# WX0_008_959DL.net
KiCad netlist of a schematic drawn in Altium Designer
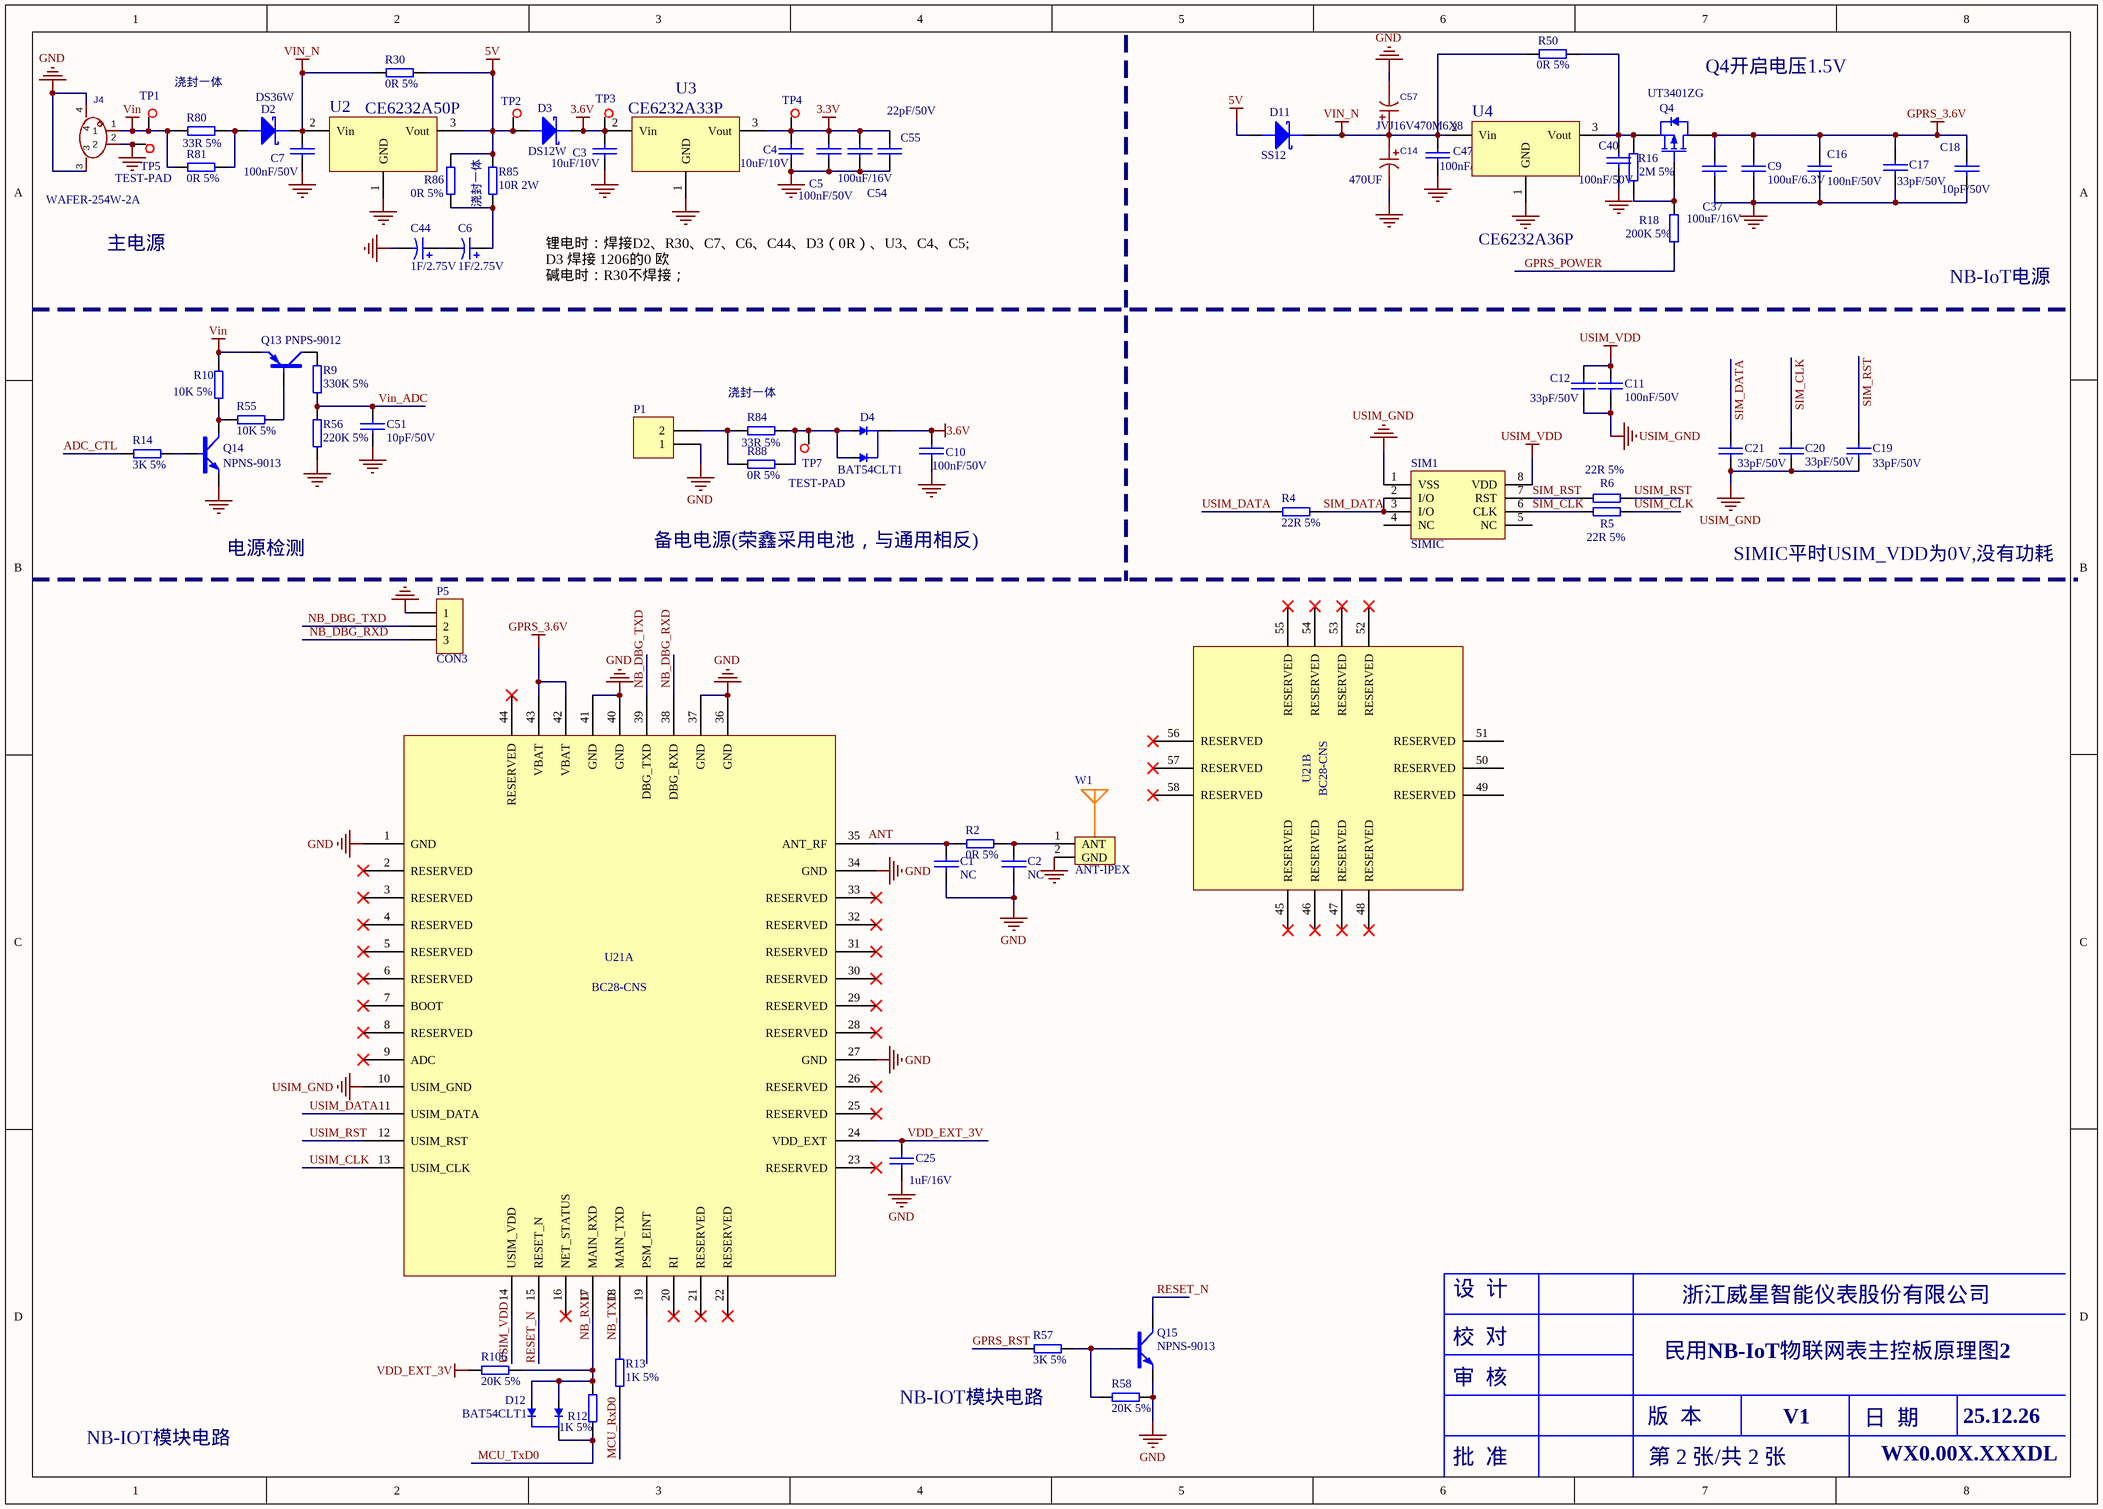
[diagram p0: WX0.008.959DL.SchDoc]

(export (version "E")
  (design (tool "Eeschema 10.0.6"))
  (components
    (comp (ref "C1")
      (value "NC")
      (footprint "CAP0402")
      (fields (field (name "PART NUMBER") "101020103-0005"))
      (libsource (lib "Database_Libs2") (part "CC03JPO9_12P"))
    )
    (comp (ref "C2")
      (value "NC")
      (footprint "CAP0402")
      (fields (field (name "PART NUMBER") "101020103-0005"))
      (libsource (lib "Database_Libs2") (part "CC03JPO9_12P"))
    )
    (comp (ref "C3")
      (value "10uF/10V")
      (footprint "CAP0603")
      (description "106pF,10 V,±10%,0603,村田,GRM188R61A106KE47D")
      (fields (field (name "PART NUMBER") "101020103-0026"))
      (libsource (lib "Database_Libs2") (part "CC03K5R6_10U"))
    )
    (comp (ref "C4")
      (value "10uF/10V")
      (footprint "CAP0603")
      (description "106pF,10 V,±10%,0603,村田,GRM188R61A106KE47D")
      (fields (field (name "PART NUMBER") "101020103-0026"))
      (libsource (lib "Database_Libs2") (part "CC03K5R6_10U"))
    )
    (comp (ref "C5")
      (value "100nF/50V")
      (footprint "CAP0603")
      (description "104pF,50 V,±10%,0603,国巨,CC0603KRX7R9BB104")
      (fields (field (name "PART NUMBER") "101020103-0021"))
      (libsource (lib "Database_Libs2") (part "CC03K7R9_100N"))
    )
    (comp (ref "C6")
      (value "1F/2.75V")
      (footprint "CAPPC_350_800_1600")
      (description "1F,2.75 V,-20%~+20%,8mm*16mm,红宝石,2.7 DMC 1 M MY4 8X16")
      (fields (field (name "PART NUMBER") "1010202-0015"))
      (libsource (lib "Database_Libs2") (part "CALM3MRDMC_1F"))
    )
    (comp (ref "C7")
      (value "100nF/50V")
      (footprint "CAP0603")
      (description "104pF,50 V,±10%,0603,国巨,CC0603KRX7R9BB104")
      (fields (field (name "PART NUMBER") "101020103-0021"))
      (libsource (lib "Database_Libs2") (part "CC03K7R9_100N"))
    )
    (comp (ref "C9")
      (value "100uF/6.3V")
      (footprint "GRM1206")
      (description "100uF,6.3 V,±20%,1206,村田,GRM31CR60J107ME39L")
      (fields (field (name "PART NUMBER") "101020101-0020"))
      (libsource (lib "Database_Libs2") (part "CC06M5R5_107P"))
    )
    (comp (ref "C10")
      (value "100nF/50V")
      (footprint "CAP0603")
      (description "104pF,50 V,±10%,0603,国巨,CC0603KRX7R9BB104")
      (fields (field (name "PART NUMBER") "101020103-0021"))
      (libsource (lib "Database_Libs2") (part "CC03K7R9_100N"))
    )
    (comp (ref "C11")
      (value "100nF/50V")
      (footprint "CAP0603")
      (description "104pF,50 V,±10%,0603,国巨,CC0603KRX7R9BB104")
      (fields (field (name "PART NUMBER") "101020103-0021"))
      (libsource (lib "Database_Libs2") (part "CC03K7R9_100N"))
    )
    (comp (ref "C12")
      (value "33pF/50V")
      (footprint "CAP0603")
      (description "33pF,50 V,±10%,0603,国巨,CC0603KRNPO9BN33")
      (fields (field (name "PART NUMBER") "101020103-0027"))
      (libsource (lib "Database_Libs2") (part "CC03KPO9_33P"))
    )
    (comp (ref "C14")
      (value "470UF")
      (footprint "CAP-SMD_BD6.3-L6.6-W6.6-LS7.3-FD-H7.7")
      (description "470UF,10v")
      (libsource (lib "JVJ16V470M6X8JVJ16V470M6X8") (part "JVJ16V470M6X8"))
    )
    (comp (ref "C16")
      (value "100nF/50V")
      (footprint "CAP0603")
      (description "104pF,50 V,±10%,0603,国巨,CC0603KRX7R9BB104")
      (fields (field (name "PART NUMBER") "101020103-0021"))
      (libsource (lib "Database_Libs2") (part "CC03K7R9_100N"))
    )
    (comp (ref "C17")
      (value "33pF/50V")
      (footprint "CAP0603")
      (description "33pF,50 V,±10%,0603,国巨,CC0603KRNPO9BN33")
      (fields (field (name "PART NUMBER") "101020103-0027"))
      (libsource (lib "Database_Libs2") (part "CC03KPO9_33P"))
    )
    (comp (ref "C18")
      (value "10pF/50V")
      (footprint "CAP0603")
      (description "10pF,50 V,±5%,0603,X7R,国巨,CC0603JRNPO9BN100")
      (fields (field (name "PART NUMBER") "101020103-0014"))
      (libsource (lib "Database_Libs2") (part "CC03JPO9_10P"))
    )
    (comp (ref "C19")
      (value "33pF/50V")
      (footprint "CAP0603")
      (description "33pF,50 V,±10%,0603,国巨,CC0603KRNPO9BN33")
      (fields (field (name "PART NUMBER") "101020103-0027"))
      (libsource (lib "Database_Libs2") (part "CC03KPO9_33P"))
    )
    (comp (ref "C20")
      (value "33pF/50V")
      (footprint "CAP0603")
      (description "33pF,50 V,±10%,0603,国巨,CC0603KRNPO9BN33")
      (fields (field (name "PART NUMBER") "101020103-0027"))
      (libsource (lib "Database_Libs2") (part "CC03KPO9_33P"))
    )
    (comp (ref "C21")
      (value "33pF/50V")
      (footprint "CAP0603")
      (description "33pF,50 V,±10%,0603,国巨,CC0603KRNPO9BN33")
      (fields (field (name "PART NUMBER") "101020103-0027"))
      (libsource (lib "Database_Libs2") (part "CC03KPO9_33P"))
    )
    (comp (ref "C25")
      (value "1uF/16V")
      (footprint "CAP0603")
      (description "105pF,16 V,±10%,0603,国巨,CC0603KRX7R7BB105")
      (fields (field (name "PART NUMBER") "101020103-0003"))
      (libsource (lib "Database_Libs2") (part "CC03K7R7_1U"))
    )
    (comp (ref "C37")
      (value "100uF/16V")
      (footprint "GRM1206")
      (libsource (lib "Database_Libs2") (part "CC06KPO7_106P"))
    )
    (comp (ref "C40")
      (value "100nF/50V")
      (footprint "CAP0603")
      (description "104pF,50 V,±10%,0603,国巨,CC0603KRX7R9BB104")
      (fields (field (name "PART NUMBER") "101020103-0021"))
      (libsource (lib "Database_Libs2") (part "CC03K7R9_100N"))
    )
    (comp (ref "C44")
      (value "1F/2.75V")
      (footprint "CAPPC_350_800_1600")
      (description "1F,2.75 V,-20%~+20%,8mm*16mm,红宝石,2.7 DMC 1 M MY4 8X16")
      (fields (field (name "PART NUMBER") "1010202-0015"))
      (libsource (lib "Database_Libs2") (part "CALM3MRDMC_1F"))
    )
    (comp (ref "C47")
      (value "100nF/50V")
      (footprint "CAP0603")
      (description "104pF,50 V,±10%,0603,国巨,CC0603KRX7R9BB104")
      (fields (field (name "PART NUMBER") "101020103-0021"))
      (libsource (lib "Database_Libs2") (part "CC03K7R9_100N"))
    )
    (comp (ref "C51")
      (value "10pF/50V")
      (footprint "CAP0603")
      (description "10pF,50 V,±5%,0603,X7R,国巨,CC0603JRNPO9BN100")
      (fields (field (name "PART NUMBER") "101020103-0014"))
      (libsource (lib "Database_Libs2") (part "CC03JPO9_10P"))
    )
    (comp (ref "C54")
      (value "100uF/16V")
      (footprint "GRM1206")
      (description "100u,16 V,±10%,1206,国巨,CC1206KRNPO7BN106P")
      (libsource (lib "Database_Libs2") (part "CC06KPO7_106P"))
    )
    (comp (ref "C55")
      (value "22pF/50V")
      (footprint "CAP0603")
      (description "22pF,50 V,±5%,0603,国巨,CC0603JRNPO9BN22")
      (fields (field (name "PART NUMBER") "101020103-0009"))
      (libsource (lib "Database_Libs2") (part "CC03JPO9_22P"))
    )
    (comp (ref "C57")
      (value "JVJ16V470M6X8")
      (footprint "CAP-SMD_BD6.3-L6.6-W6.6-LS7.3-FD-H7.7")
      (libsource (lib "JVJ16V470M6X8JVJ16V470M6X8") (part "JVJ16V470M6X8"))
    )
    (comp (ref "D2")
      (value "DS36W")
      (footprint "SOD-123FL")
      (description "DS36W,SOD123-FL,3 A,42 V,60 V,浙江领晨科技有限公司,DS36W")
      (fields (field (name "PART NUMBER") "101040101-0055"))
      (libsource (lib "Database_Libs2") (part "02_DS12W"))
    )
    (comp (ref "D3")
      (value "DS12W")
      (footprint "SOD-123FL")
      (description "DS12W,SOD-123FL,1 A,0.55 V,20 V,领晨科技,DS12W")
      (fields (field (name "PART NUMBER") "101040101-0048"))
      (libsource (lib "Database_Libs2") (part "02_DS12W"))
    )
    (comp (ref "D4")
      (value "BAT54CLT1")
      (footprint "SOT-23")
      (description "BAT54CLT1，SOT23-3,SOT23-3,0.2 A,0.8 V,30 V,安森美,BAT54CLT1")
      (fields (field (name "PART NUMBER") "101040101-0038"))
      (libsource (lib "Database_Libs2") (part "02_BAT54CLT1"))
    )
    (comp (ref "D11")
      (value "SS12")
      (footprint "DO-214AC")
      (description "SS12,DO-214AC,1 A,0.55 V,20 V,昶鑫,SS12")
      (fields (field (name "PART NUMBER") "101040101-0009"))
      (libsource (lib "Database_Libs2") (part "02_SS12"))
    )
    (comp (ref "D12")
      (value "BAT54CLT1")
      (footprint "SOT-23")
      (description "BAT54CLT1，SOT23-3,SOT23-3,0.2 A,0.8 V,30 V,安森美,BAT54CLT1")
      (fields (field (name "PART NUMBER") "101040101-0038"))
      (libsource (lib "Database_Libs2") (part "02_BAT54CLT1"))
    )
    (comp (ref "J4")
      (value "WAFER-254W-2A")
      (footprint "XH 2.54")
      (libsource (lib "WAFER-254W-2AWAFER-254W-2A") (part "WAFER-254W-2A"))
    )
    (comp (ref "P1")
      (value "~")
      (footprint "SMT2-2.0")
      (description "2.0-2AW,直插弯座，2PIN，脚间距2mm，带防翘起,公头,单排,2.0-2AW;直插弯座，2PIN,脚间距2mm，带防翘起")
      (fields (field (name "PART NUMBER") "1010902-0105"))
      (libsource (lib "Database_Libs1") (part "PH200_1*2R"))
    )
    (comp (ref "P5")
      (value "CON3")
      (footprint "SIP-3")
      (description "Connector")
      (libsource (lib "Miscellaneous Devices") (part "CON3"))
    )
    (comp (ref "Q4")
      (value "UT3401ZG")
      (footprint "SOT-23")
      (description "UT3401ZG,P-MOS,SOT-23,UTC,UT3401ZG")
      (fields (field (name "PART NUMBER") "101040201-0013"))
      (libsource (lib "Database_Libs2") (part "03_P-UT3401ZG"))
    )
    (comp (ref "Q13")
      (value "PNPS-9012")
      (footprint "SOT-23")
      (description "9012,PNP,SOT-23,JCET;长电,S9012")
      (fields (field (name "PART NUMBER") "101040201-0001"))
      (libsource (lib "Database_Libs2") (part "03_PNPS-9012"))
    )
    (comp (ref "Q14")
      (value "NPNS-9013")
      (footprint "SOT-23")
      (description "9013,NPN,SOT-23,长电,S9013")
      (fields (field (name "PART NUMBER") "101040201-0002"))
      (libsource (lib "Database_Libs2") (part "03_NPNS-9013"))
    )
    (comp (ref "Q15")
      (value "NPNS-9013")
      (footprint "SOT-23")
      (description "9013,NPN,SOT-23,长电,S9013")
      (fields (field (name "PART NUMBER") "101040201-0002"))
      (libsource (lib "Database_Libs2") (part "03_NPNS-9013"))
    )
    (comp (ref "R2")
      (value "0R 5%")
      (footprint "RES0603")
      (description "国巨,±5%,0603,,155 ℃,-55 ℃,RC0603J2-070RL,无铅,200 ppm/℃,1/10W,,0R")
      (fields (field (name "PART NUMBER") "101010103-0001"))
      (libsource (lib "Database_Libs2") (part "RC03J_0R"))
    )
    (comp (ref "R4")
      (value "22R 5%")
      (footprint "RES0603")
      (description "国巨,±5%,0603,,155 ℃,-55 ℃,RC0603JR-0722RL,无铅,200 ppm/℃,1/10W,,22欧")
      (fields (field (name "PART NUMBER") "101010103-0009"))
      (libsource (lib "Database_Libs2") (part "RC03J_22R"))
    )
    (comp (ref "R5")
      (value "22R 5%")
      (footprint "RES0603")
      (description "国巨,±5%,0603,,155 ℃,-55 ℃,RC0603JR-0722RL,无铅,200 ppm/℃,1/10W,,22欧")
      (fields (field (name "PART NUMBER") "101010103-0009"))
      (libsource (lib "Database_Libs2") (part "RC03J_22R"))
    )
    (comp (ref "R6")
      (value "22R 5%")
      (footprint "RES0603")
      (description "国巨,±5%,0603,,155 ℃,-55 ℃,RC0603JR-0722RL,无铅,200 ppm/℃,1/10W,,22欧")
      (fields (field (name "PART NUMBER") "101010103-0009"))
      (libsource (lib "Database_Libs2") (part "RC03J_22R"))
    )
    (comp (ref "R9")
      (value "330K 5%")
      (footprint "RES0603")
      (description "330K,±5%,1/10W,0603,国巨,RC0603JR-07330KL")
      (fields (field (name "PART NUMBER") "101010103-0066"))
      (libsource (lib "Database_Libs2") (part "RC03J_330K"))
    )
    (comp (ref "R10")
      (value "10K 5%")
      (footprint "RES0603")
      (description "国巨,±5%,0603,,155 ℃,-55 ℃,RC0603JR-0710KL,无铅,200 ppm/℃,1/10W,,10K")
      (fields (field (name "PART NUMBER") "101010103-0003"))
      (libsource (lib "Database_Libs2") (part "RC03J_10K"))
    )
    (comp (ref "R12")
      (value "1K 5%")
      (footprint "RES0603")
      (description "220K,±5%,1/10W,0603,国巨,RC0603JR-07220KL")
      (fields (field (name "PART NUMBER") "101010103-0044"))
      (libsource (lib "Database_Libs2") (part "RC03J_220K"))
    )
    (comp (ref "R13")
      (value "1K 5%")
      (footprint "RES0603")
      (description "220K,±5%,1/10W,0603,国巨,RC0603JR-07220KL")
      (fields (field (name "PART NUMBER") "101010103-0044"))
      (libsource (lib "Database_Libs2") (part "RC03J_220K"))
    )
    (comp (ref "R14")
      (value "3K 5%")
      (footprint "RES0603")
      (description "国巨,±5%,0603,,155 ℃,-55 ℃,RC0603JR-073KL,无铅,100 ppm/℃,1/10W,,3K")
      (fields (field (name "PART NUMBER") "101010103-0006"))
      (libsource (lib "Database_Libs2") (part "RC03J_3K"))
    )
    (comp (ref "R16")
      (value "2M 5%")
      (footprint "RES0603")
      (description "国巨,±5%,0603,,155 ℃,-55 ℃,RC0603JR-072ML,含铅,100 ppm/℃,1/10W,,2M")
      (fields (field (name "PART NUMBER") "101010103-0025"))
      (libsource (lib "Database_Libs2") (part "RC03J_2M"))
    )
    (comp (ref "R18")
      (value "200K 5%")
      (footprint "RES0603")
      (description "200K,±5%,1/10W,0603,国巨,RC0603JR-07200KL")
      (fields (field (name "PART NUMBER") "101010103-0034"))
      (libsource (lib "Database_Libs2") (part "RC03J_200K"))
    )
    (comp (ref "R30")
      (value "0R 5%")
      (footprint "RES1206")
      (description "0Ω,±5%,1/4W,1206,国巨,RC1206JR-070RL")
      (fields (field (name "PART NUMBER") "101010101-0013"))
      (libsource (lib "Database_Libs2") (part "RC06J_0R"))
    )
    (comp (ref "R50")
      (value "0R 5%")
      (footprint "RES1206")
      (description "0Ω,±5%,1/4W,1206,国巨,RC1206JR-070RL")
      (fields (field (name "PART NUMBER") "101010101-0013"))
      (libsource (lib "Database_Libs2") (part "RC06J_0R"))
    )
    (comp (ref "R55")
      (value "10K 5%")
      (footprint "RES0603")
      (description "国巨,±5%,0603,,155 ℃,-55 ℃,RC0603JR-0710KL,无铅,200 ppm/℃,1/10W,,10K")
      (fields (field (name "PART NUMBER") "101010103-0003"))
      (libsource (lib "Database_Libs2") (part "RC03J_10K"))
    )
    (comp (ref "R56")
      (value "220K 5%")
      (footprint "RES0603")
      (description "220K,±5%,1/10W,0603,国巨,RC0603JR-07220KL")
      (fields (field (name "PART NUMBER") "101010103-0044"))
      (libsource (lib "Database_Libs2") (part "RC03J_220K"))
    )
    (comp (ref "R57")
      (value "3K 5%")
      (footprint "RES0603")
      (description "国巨,±5%,0603,,155 ℃,-55 ℃,RC0603JR-073KL,无铅,100 ppm/℃,1/10W,,3K")
      (fields (field (name "PART NUMBER") "101010103-0006"))
      (libsource (lib "Database_Libs2") (part "RC03J_3K"))
    )
    (comp (ref "R58")
      (value "20K 5%")
      (footprint "RES0603")
      (description "国巨,±5%,0603,,155 ℃,-55 ℃,RC0603JR-0720KL,无铅,200 ppm/℃,1/10W,,20K")
      (fields (field (name "PART NUMBER") "101010103-0004"))
      (libsource (lib "Database_Libs2") (part "RC03J_20K"))
    )
    (comp (ref "R80")
      (value "33R 5%")
      (footprint "金属膜电阻")
      (description "国巨,±5%,0603,,155 ℃,-55 ℃,RC0603JR-0722RL,无铅,200 ppm/℃,1/10W,,22欧")
      (fields (field (name "PART NUMBER") "101010103-0009"))
      (libsource (lib "Database_Libs2") (part "RC03J_22R"))
    )
    (comp (ref "R81")
      (value "0R 5%")
      (footprint "RES1206")
      (description "0Ω,±5%,1/4W,1206,国巨,RC1206JR-070RL")
      (fields (field (name "PART NUMBER") "101010101-0013"))
      (libsource (lib "Database_Libs2") (part "RC06J_0R"))
    )
    (comp (ref "R84")
      (value "33R 5%")
      (footprint "金属膜电阻")
      (description "国巨,±5%,0603,,155 ℃,-55 ℃,RC0603JR-0722RL,无铅,200 ppm/℃,1/10W,,22欧")
      (fields (field (name "PART NUMBER") "101010103-0009"))
      (libsource (lib "Database_Libs2") (part "RC03J_22R"))
    )
    (comp (ref "R85")
      (value "10R 2W")
      (footprint "金属膜电阻")
      (description "国巨,±5%,0603,,155 ℃,-55 ℃,RC0603JR-0722RL,无铅,200 ppm/℃,1/10W,,22欧")
      (fields (field (name "PART NUMBER") "101010103-0009"))
      (libsource (lib "Database_Libs2") (part "RC03J_22R"))
    )
    (comp (ref "R86")
      (value "0R 5%")
      (footprint "RES1206")
      (description "0Ω,±5%,1/4W,1206,国巨,RC1206JR-070RL")
      (fields (field (name "PART NUMBER") "101010101-0013"))
      (libsource (lib "Database_Libs2") (part "RC06J_0R"))
    )
    (comp (ref "R88")
      (value "0R 5%")
      (footprint "RES1206")
      (description "0Ω,±5%,1/4W,1206,国巨,RC1206JR-070RL")
      (fields (field (name "PART NUMBER") "101010101-0013"))
      (libsource (lib "Database_Libs2") (part "RC06J_0R"))
    )
    (comp (ref "R106")
      (value "20K 5%")
      (footprint "RES0603")
      (description "国巨,±5%,0603,,155 ℃,-55 ℃,RC0603JR-0720KL,无铅,200 ppm/℃,1/10W,,20K")
      (fields (field (name "PART NUMBER") "101010103-0004"))
      (libsource (lib "Database_Libs2") (part "RC03J_20K"))
    )
    (comp (ref "SIM1")
      (value "SIMIC")
      (footprint "SIMIC")
      (description "SIMIC虚拟器件")
      (fields (field (name "PART NUMBER") "AD_XN_SIMIC_01"))
      (libsource (lib "Database_Libs2") (part "05_SIMIC"))
    )
    (comp (ref "TP1")
      (value "TEST-PAD")
      (footprint "TEST-PAD")
      (description "单面焊盘测试点")
      (fields (field (name "PART NUMBER") "AD_WXHJ_TEST-PAD_01"))
      (libsource (lib "Database_Libs2") (part "TEST-PAD"))
    )
    (comp (ref "TP2")
      (value "TEST-PAD")
      (footprint "TEST-PAD")
      (description "单面焊盘测试点")
      (fields (field (name "PART NUMBER") "AD_WXHJ_TEST-PAD_01"))
      (libsource (lib "Database_Libs2") (part "TEST-PAD"))
    )
    (comp (ref "TP3")
      (value "TEST-PAD")
      (footprint "TEST-PAD")
      (description "单面焊盘测试点")
      (fields (field (name "PART NUMBER") "AD_WXHJ_TEST-PAD_01"))
      (libsource (lib "Database_Libs2") (part "TEST-PAD"))
    )
    (comp (ref "TP4")
      (value "TEST-PAD")
      (footprint "TEST-PAD")
      (description "单面焊盘测试点")
      (fields (field (name "PART NUMBER") "AD_WXHJ_TEST-PAD_01"))
      (libsource (lib "Database_Libs2") (part "TEST-PAD"))
    )
    (comp (ref "TP5")
      (value "TEST-PAD")
      (footprint "TEST-PAD")
      (description "单面焊盘测试点")
      (fields (field (name "PART NUMBER") "AD_WXHJ_TEST-PAD_01"))
      (libsource (lib "Database_Libs2") (part "TEST-PAD"))
    )
    (comp (ref "TP7")
      (value "TEST-PAD")
      (footprint "TEST-PAD")
      (description "单面焊盘测试点")
      (fields (field (name "PART NUMBER") "AD_WXHJ_TEST-PAD_01"))
      (libsource (lib "Database_Libs2") (part "TEST-PAD"))
    )
    (comp (ref "U2")
      (value "CE6232A50P")
      (footprint "SOT-89")
      (fields (field (name "PART NUMBER") "1010503-0013"))
      (libsource (lib "Database_Libs2") (part "02_S-1206B50-U3"))
    )
    (comp (ref "U3")
      (value "CE6232A33P")
      (footprint "SOT-89")
      (fields (field (name "PART NUMBER") "1010503-0002"))
      (libsource (lib "Database_Libs2") (part "02_S-1206B33-U3T1G"))
    )
    (comp (ref "U4")
      (value "CE6232A36P")
      (footprint "SOT-89")
      (description "CE6232A36P,CE6232A36P,SOT89-3,8 V,1.8 V,0.11 V,3.6 V,600mA,0.8 uA,南京芯力微电子有限公司")
      (fields (field (name "PART NUMBER") "1010503-0031"))
      (libsource (lib "Database_Libs2") (part "02_CE6232A36P"))
    )
    (comp (ref "U21")
      (value "BC28-CNS")
      (footprint "BC28-CNS")
      (description "BC28-CNS Moudle 58Pin 15.8X17.7mm H2.2mm RO")
      (fields (field (name "MANUFACTURER") "Quectel"))
      (libsource (lib "") (part "BC28-CNS_1"))
    )
    (comp (ref "W1")
      (value "ANT-IPEX")
      (footprint "Connect_WX:ANT-IPEX")
      (description "IPEX，配GPRS天线转接线")
      (fields (field (name "PART NUMBER") "1010902-0053"))
      (libsource (lib "Database_Libs2") (part "IPEX"))
    )
  )
  (nets
    (net (code "1") (name "/ADC_CTL") (class "Default")
      (node (ref "R14") (pin "1") (pinfunction "1_1") (pintype "passive"))
    )
    (net (code "3") (name "/GPRS_POWER") (class "Default")
      (node (ref "R18") (pin "1") (pinfunction "1_1") (pintype "passive"))
    )
    (net (code "4") (name "/GPRS_RST") (class "Default")
      (node (ref "R57") (pin "1") (pinfunction "1_1") (pintype "passive"))
    )
    (net (code "5") (name "/MCU_RxD0") (class "Default")
      (node (ref "R13") (pin "1") (pinfunction "1_1") (pintype "passive"))
    )
    (net (code "6") (name "/MCU_TxD0") (class "Default")
      (node (ref "D12") (pin "3") (pinfunction "C_3") (pintype "passive"))
      (node (ref "R12") (pin "2") (pinfunction "2_2") (pintype "passive"))
    )
    (net (code "7") (name "/NB_DBG_RXD") (class "Default")
      (node (ref "P5") (pin "3") (pinfunction "3_3") (pintype "passive"))
      (node (ref "U21") (pin "38") (pinfunction "DBG_RXD_38") (pintype "passive"))
    )
    (net (code "8") (name "/NB_DBG_TXD") (class "Default")
      (node (ref "P5") (pin "2") (pinfunction "2_2") (pintype "passive"))
      (node (ref "U21") (pin "39") (pinfunction "DBG_TXD_39") (pintype "passive"))
    )
    (net (code "9") (name "/NB_RXD") (class "Default")
      (node (ref "D12") (pin "1") (pinfunction "A_1") (pintype "passive"))
      (node (ref "D12") (pin "2") (pinfunction "A_2") (pintype "passive"))
      (node (ref "R106") (pin "2") (pinfunction "2_2") (pintype "passive"))
      (node (ref "R12") (pin "1") (pinfunction "1_1") (pintype "passive"))
      (node (ref "U21") (pin "17") (pinfunction "MAIN_RXD_17") (pintype "passive"))
    )
    (net (code "10") (name "/NB_TXD") (class "Default")
      (node (ref "R13") (pin "2") (pinfunction "2_2") (pintype "passive"))
      (node (ref "U21") (pin "18") (pinfunction "MAIN_TXD_18") (pintype "passive"))
    )
    (net (code "11") (name "/RESET_N") (class "Default")
      (node (ref "Q15") (pin "3") (pinfunction "C_3") (pintype "passive"))
      (node (ref "U21") (pin "15") (pinfunction "RESET_N_15") (pintype "passive"))
    )
    (net (code "12") (name "/SIM_CLK") (class "Default")
      (node (ref "C20") (pin "1") (pinfunction "1_1") (pintype "passive"))
      (node (ref "R5") (pin "1") (pinfunction "1_1") (pintype "passive"))
      (node (ref "SIM1") (pin "6") (pinfunction "CLK_6") (pintype "passive"))
    )
    (net (code "13") (name "/SIM_DATA") (class "Default")
      (node (ref "C21") (pin "1") (pinfunction "1_1") (pintype "passive"))
      (node (ref "R4") (pin "2") (pinfunction "2_2") (pintype "passive"))
      (node (ref "SIM1") (pin "2") (pinfunction "I/O_2") (pintype "passive"))
      (node (ref "SIM1") (pin "3") (pinfunction "I/O_3") (pintype "passive"))
    )
    (net (code "14") (name "/SIM_RST") (class "Default")
      (node (ref "C19") (pin "1") (pinfunction "1_1") (pintype "passive"))
      (node (ref "R6") (pin "1") (pinfunction "1_1") (pintype "passive"))
      (node (ref "SIM1") (pin "7") (pinfunction "RST_7") (pintype "passive"))
    )
    (net (code "15") (name "/USIM_CLK") (class "Default")
      (node (ref "R5") (pin "2") (pinfunction "2_2") (pintype "passive"))
      (node (ref "U21") (pin "13") (pinfunction "USIM_CLK_13") (pintype "passive"))
    )
    (net (code "16") (name "/USIM_DATA") (class "Default")
      (node (ref "R4") (pin "1") (pinfunction "1_1") (pintype "passive"))
      (node (ref "U21") (pin "11") (pinfunction "USIM_DATA_11") (pintype "passive"))
    )
    (net (code "17") (name "/USIM_RST") (class "Default")
      (node (ref "R6") (pin "2") (pinfunction "2_2") (pintype "passive"))
      (node (ref "U21") (pin "12") (pinfunction "USIM_RST_12") (pintype "passive"))
    )
    (net (code "18") (name "/Vin_ADC") (class "Default")
      (node (ref "C51") (pin "2") (pinfunction "2_2") (pintype "passive"))
      (node (ref "R56") (pin "1") (pinfunction "1_1") (pintype "passive"))
      (node (ref "R9") (pin "2") (pinfunction "2_2") (pintype "passive"))
    )
    (net (code "19") (name "3.3V") (class "Default")
      (node (ref "C4") (pin "1") (pinfunction "1_1") (pintype "passive"))
      (node (ref "C5") (pin "1") (pinfunction "1_1") (pintype "passive"))
      (node (ref "C54") (pin "1") (pinfunction "1_1") (pintype "passive"))
      (node (ref "C55") (pin "1") (pinfunction "1_1") (pintype "passive"))
      (node (ref "TP4") (pin "1") (pinfunction "1_1") (pintype "passive"))
      (node (ref "U3") (pin "3") (pinfunction "Vout_3") (pintype "passive"))
    )
    (net (code "20") (name "3.6V") (class "Default")
      (node (ref "C10") (pin "1") (pinfunction "1_1") (pintype "passive"))
      (node (ref "C3") (pin "1") (pinfunction "1_1") (pintype "passive"))
      (node (ref "D3") (pin "2") (pinfunction "2_2") (pintype "passive"))
      (node (ref "D4") (pin "3") (pinfunction "C_3") (pintype "passive"))
      (node (ref "TP3") (pin "1") (pinfunction "1_1") (pintype "passive"))
      (node (ref "U3") (pin "2") (pinfunction "Vin_2") (pintype "passive"))
    )
    (net (code "21") (name "5V") (class "Default")
      (node (ref "D11") (pin "1") (pinfunction "1_1") (pintype "passive"))
      (node (ref "D3") (pin "1") (pinfunction "1_1") (pintype "passive"))
      (node (ref "R30") (pin "2") (pinfunction "2_2") (pintype "passive"))
      (node (ref "R85") (pin "2") (pinfunction "2_2") (pintype "passive"))
      (node (ref "R86") (pin "2") (pinfunction "2_2") (pintype "passive"))
      (node (ref "TP2") (pin "1") (pinfunction "1_1") (pintype "passive"))
      (node (ref "U2") (pin "3") (pinfunction "Vout_3") (pintype "passive"))
    )
    (net (code "22") (name "GND") (class "Default")
      (node (ref "C1") (pin "1") (pinfunction "1_1") (pintype "passive"))
      (node (ref "C10") (pin "2") (pinfunction "2_2") (pintype "passive"))
      (node (ref "C14") (pin "2") (pinfunction "2_2") (pintype "passive"))
      (node (ref "C16") (pin "2") (pinfunction "2_2") (pintype "passive"))
      (node (ref "C17") (pin "2") (pinfunction "2_2") (pintype "passive"))
      (node (ref "C18") (pin "2") (pinfunction "2_2") (pintype "passive"))
      (node (ref "C2") (pin "1") (pinfunction "1_1") (pintype "passive"))
      (node (ref "C25") (pin "2") (pinfunction "2_2") (pintype "passive"))
      (node (ref "C3") (pin "2") (pinfunction "2_2") (pintype "passive"))
      (node (ref "C37") (pin "2") (pinfunction "2_2") (pintype "passive"))
      (node (ref "C4") (pin "2") (pinfunction "2_2") (pintype "passive"))
      (node (ref "C40") (pin "2") (pinfunction "2_2") (pintype "passive"))
      (node (ref "C44") (pin "2") (pinfunction "2_2") (pintype "passive"))
      (node (ref "C47") (pin "2") (pinfunction "2_2") (pintype "passive"))
      (node (ref "C5") (pin "2") (pinfunction "2_2") (pintype "passive"))
      (node (ref "C51") (pin "1") (pinfunction "1_1") (pintype "passive"))
      (node (ref "C54") (pin "2") (pinfunction "2_2") (pintype "passive"))
      (node (ref "C55") (pin "2") (pinfunction "2_2") (pintype "passive"))
      (node (ref "C57") (pin "2") (pinfunction "2_2") (pintype "passive"))
      (node (ref "C7") (pin "2") (pinfunction "2_2") (pintype "passive"))
      (node (ref "C9") (pin "2") (pinfunction "2_2") (pintype "passive"))
      (node (ref "J4") (pin "2") (pinfunction "2_2") (pintype "passive"))
      (node (ref "J4") (pin "3") (pinfunction "3_3") (pintype "passive"))
      (node (ref "J4") (pin "4") (pinfunction "4_4") (pintype "passive"))
      (node (ref "P1") (pin "1") (pinfunction "1_1") (pintype "passive"))
      (node (ref "P5") (pin "1") (pinfunction "1_1") (pintype "passive"))
      (node (ref "Q14") (pin "2") (pinfunction "E_2") (pintype "passive"))
      (node (ref "Q15") (pin "2") (pinfunction "E_2") (pintype "passive"))
      (node (ref "R56") (pin "2") (pinfunction "2_2") (pintype "passive"))
      (node (ref "R58") (pin "2") (pinfunction "2_2") (pintype "passive"))
      (node (ref "TP5") (pin "1") (pinfunction "1_1") (pintype "passive"))
      (node (ref "U2") (pin "1") (pinfunction "GND_1") (pintype "passive"))
      (node (ref "U21") (pin "1") (pinfunction "GND_1") (pintype "passive"))
      (node (ref "U21") (pin "27") (pinfunction "GND_27") (pintype "passive"))
      (node (ref "U21") (pin "34") (pinfunction "GND_34") (pintype "passive"))
      (node (ref "U21") (pin "36") (pinfunction "GND_36") (pintype "passive"))
      (node (ref "U21") (pin "37") (pinfunction "GND_37") (pintype "passive"))
      (node (ref "U21") (pin "40") (pinfunction "GND_40") (pintype "passive"))
      (node (ref "U21") (pin "41") (pinfunction "GND_41") (pintype "passive"))
      (node (ref "U3") (pin "1") (pinfunction "GND_1") (pintype "passive"))
      (node (ref "U4") (pin "1") (pinfunction "GND_1") (pintype "passive"))
      (node (ref "W1") (pin "2") (pinfunction "GND_2") (pintype "passive"))
    )
    (net (code "23") (name "GPRS_3.6V") (class "Default")
      (node (ref "C16") (pin "1") (pinfunction "1_1") (pintype "passive"))
      (node (ref "C17") (pin "1") (pinfunction "1_1") (pintype "passive"))
      (node (ref "C18") (pin "1") (pinfunction "1_1") (pintype "passive"))
      (node (ref "C37") (pin "1") (pinfunction "1_1") (pintype "passive"))
      (node (ref "C9") (pin "1") (pinfunction "1_1") (pintype "passive"))
      (node (ref "Q4") (pin "3") (pinfunction "D_3") (pintype "passive"))
      (node (ref "U21") (pin "42") (pinfunction "VBAT_42") (pintype "passive"))
      (node (ref "U21") (pin "43") (pinfunction "VBAT_43") (pintype "passive"))
    )
    (net (code "24") (name "Net-(C6-Pad1)") (class "Default")
      (node (ref "C6") (pin "1") (pinfunction "1_1") (pintype "passive"))
      (node (ref "R85") (pin "1") (pinfunction "1_1") (pintype "passive"))
      (node (ref "R86") (pin "1") (pinfunction "1_1") (pintype "passive"))
    )
    (net (code "25") (name "Net-(C44-Pad1)") (class "Default")
      (node (ref "C44") (pin "1") (pinfunction "1_1") (pintype "passive"))
      (node (ref "C6") (pin "2") (pinfunction "2_2") (pintype "passive"))
    )
    (net (code "26") (name "Net-(D2-Pad1)") (class "Default")
      (node (ref "D2") (pin "1") (pinfunction "1_1") (pintype "passive"))
      (node (ref "R80") (pin "2") (pinfunction "2_2") (pintype "passive"))
      (node (ref "R81") (pin "2") (pinfunction "2_2") (pintype "passive"))
    )
    (net (code "27") (name "Net-(D4-A-Pad1)") (class "Default")
      (node (ref "D4") (pin "1") (pinfunction "A_1") (pintype "passive"))
      (node (ref "D4") (pin "2") (pinfunction "A_2") (pintype "passive"))
      (node (ref "R84") (pin "2") (pinfunction "2_2") (pintype "passive"))
      (node (ref "R88") (pin "2") (pinfunction "2_2") (pintype "passive"))
      (node (ref "TP7") (pin "1") (pinfunction "1_1") (pintype "passive"))
    )
    (net (code "28") (name "Net-(P1-Pad2)") (class "Default")
      (node (ref "P1") (pin "2") (pinfunction "2_2") (pintype "passive"))
      (node (ref "R84") (pin "1") (pinfunction "1_1") (pintype "passive"))
      (node (ref "R88") (pin "1") (pinfunction "1_1") (pintype "passive"))
    )
    (net (code "29") (name "Net-(Q4-G)") (class "Default")
      (node (ref "Q4") (pin "1") (pinfunction "G_1") (pintype "passive"))
      (node (ref "R16") (pin "1") (pinfunction "1_1") (pintype "passive"))
      (node (ref "R18") (pin "2") (pinfunction "2_2") (pintype "passive"))
    )
    (net (code "30") (name "Net-(Q4-S)") (class "Default")
      (node (ref "C40") (pin "1") (pinfunction "1_1") (pintype "passive"))
      (node (ref "Q4") (pin "2") (pinfunction "S_2") (pintype "passive"))
      (node (ref "R16") (pin "2") (pinfunction "2_2") (pintype "passive"))
      (node (ref "R50") (pin "2") (pinfunction "2_2") (pintype "passive"))
      (node (ref "U4") (pin "3") (pinfunction "Vout_3") (pintype "passive"))
    )
    (net (code "31") (name "Net-(Q13-B)") (class "Default")
      (node (ref "Q13") (pin "1") (pinfunction "B_1") (pintype "passive"))
      (node (ref "R55") (pin "2") (pinfunction "2_2") (pintype "passive"))
    )
    (net (code "32") (name "Net-(Q13-C)") (class "Default")
      (node (ref "Q13") (pin "3") (pinfunction "C_3") (pintype "passive"))
      (node (ref "R9") (pin "1") (pinfunction "1_1") (pintype "passive"))
    )
    (net (code "33") (name "Net-(Q14-B)") (class "Default")
      (node (ref "Q14") (pin "1") (pinfunction "B_1") (pintype "passive"))
      (node (ref "R14") (pin "2") (pinfunction "2_2") (pintype "passive"))
    )
    (net (code "34") (name "Net-(Q14-C)") (class "Default")
      (node (ref "Q14") (pin "3") (pinfunction "C_3") (pintype "passive"))
      (node (ref "R10") (pin "1") (pinfunction "1_1") (pintype "passive"))
      (node (ref "R55") (pin "1") (pinfunction "1_1") (pintype "passive"))
    )
    (net (code "35") (name "Net-(Q15-B)") (class "Default")
      (node (ref "Q15") (pin "1") (pinfunction "B_1") (pintype "passive"))
      (node (ref "R57") (pin "2") (pinfunction "2_2") (pintype "passive"))
      (node (ref "R58") (pin "1") (pinfunction "1_1") (pintype "passive"))
    )
    (net (code "36") (name "Net-(U21A-ANT_RF)") (class "Default")
      (node (ref "C1") (pin "2") (pinfunction "2_2") (pintype "passive"))
      (node (ref "R2") (pin "1") (pinfunction "1_1") (pintype "passive"))
      (node (ref "U21") (pin "35") (pinfunction "ANT_RF_35") (pintype "passive"))
    )
    (net (code "37") (name "Net-(W1-ANT)") (class "Default")
      (node (ref "C2") (pin "2") (pinfunction "2_2") (pintype "passive"))
      (node (ref "R2") (pin "2") (pinfunction "2_2") (pintype "passive"))
      (node (ref "W1") (pin "1") (pinfunction "ANT_1") (pintype "passive"))
    )
    (net (code "38") (name "USIM_GND") (class "Default")
      (node (ref "C11") (pin "2") (pinfunction "2_2") (pintype "passive"))
      (node (ref "C12") (pin "2") (pinfunction "2_2") (pintype "passive"))
      (node (ref "C19") (pin "2") (pinfunction "2_2") (pintype "passive"))
      (node (ref "C20") (pin "2") (pinfunction "2_2") (pintype "passive"))
      (node (ref "C21") (pin "2") (pinfunction "2_2") (pintype "passive"))
      (node (ref "SIM1") (pin "1") (pinfunction "VSS_1") (pintype "passive"))
      (node (ref "U21") (pin "10") (pinfunction "USIM_GND_10") (pintype "passive"))
    )
    (net (code "39") (name "USIM_VDD") (class "Default")
      (node (ref "C11") (pin "1") (pinfunction "1_1") (pintype "passive"))
      (node (ref "C12") (pin "1") (pinfunction "1_1") (pintype "passive"))
      (node (ref "SIM1") (pin "8") (pinfunction "VDD_8") (pintype "passive"))
      (node (ref "U21") (pin "14") (pinfunction "USIM_VDD_14") (pintype "passive"))
    )
    (net (code "40") (name "VDD_EXT_3V") (class "Default")
      (node (ref "C25") (pin "1") (pinfunction "1_1") (pintype "passive"))
      (node (ref "R106") (pin "1") (pinfunction "1_1") (pintype "passive"))
      (node (ref "U21") (pin "24") (pinfunction "VDD_EXT_24") (pintype "passive"))
    )
    (net (code "41") (name "VIN_N") (class "Default")
      (node (ref "C14") (pin "1") (pinfunction "1_1") (pintype "passive"))
      (node (ref "C47") (pin "1") (pinfunction "1_1") (pintype "passive"))
      (node (ref "C57") (pin "1") (pinfunction "1_1") (pintype "passive"))
      (node (ref "C7") (pin "1") (pinfunction "1_1") (pintype "passive"))
      (node (ref "D11") (pin "2") (pinfunction "2_2") (pintype "passive"))
      (node (ref "D2") (pin "2") (pinfunction "2_2") (pintype "passive"))
      (node (ref "R30") (pin "1") (pinfunction "1_1") (pintype "passive"))
      (node (ref "R50") (pin "1") (pinfunction "1_1") (pintype "passive"))
      (node (ref "U2") (pin "2") (pinfunction "Vin_2") (pintype "passive"))
      (node (ref "U4") (pin "2") (pinfunction "Vin_2") (pintype "passive"))
    )
    (net (code "42") (name "Vin") (class "Default")
      (node (ref "J4") (pin "1") (pinfunction "1_1") (pintype "passive"))
      (node (ref "Q13") (pin "2") (pinfunction "E_2") (pintype "passive"))
      (node (ref "R10") (pin "2") (pinfunction "2_2") (pintype "passive"))
      (node (ref "R80") (pin "1") (pinfunction "1_1") (pintype "passive"))
      (node (ref "R81") (pin "1") (pinfunction "1_1") (pintype "passive"))
      (node (ref "TP1") (pin "1") (pinfunction "1_1") (pintype "passive"))
    )
    (net (code "43") (name "unconnected-(SIM1-NC-Pad4)") (class "Default")
      (node (ref "SIM1") (pin "4") (pinfunction "NC_4") (pintype "passive"))
    )
    (net (code "44") (name "unconnected-(SIM1-NC-Pad5)") (class "Default")
      (node (ref "SIM1") (pin "5") (pinfunction "NC_5") (pintype "passive"))
    )
    (net (code "45") (name "unconnected-(U21A-ADC-Pad9)") (class "Default")
      (node (ref "U21") (pin "9") (pinfunction "ADC_9") (pintype "passive+no_connect"))
    )
    (net (code "46") (name "unconnected-(U21A-BOOT-Pad7)") (class "Default")
      (node (ref "U21") (pin "7") (pinfunction "BOOT_7") (pintype "passive+no_connect"))
    )
    (net (code "47") (name "unconnected-(U21A-NET_STATUS-Pad16)") (class "Default")
      (node (ref "U21") (pin "16") (pinfunction "NET_STATUS_16") (pintype "passive+no_connect"))
    )
    (net (code "48") (name "unconnected-(U21A-PSM_EINT-Pad19)") (class "Default")
      (node (ref "U21") (pin "19") (pinfunction "PSM_EINT_19") (pintype "passive"))
    )
    (net (code "49") (name "unconnected-(U21A-RESERVED-Pad2)") (class "Default")
      (node (ref "U21") (pin "2") (pinfunction "RESERVED_2") (pintype "passive+no_connect"))
    )
    (net (code "50") (name "unconnected-(U21A-RESERVED-Pad3)") (class "Default")
      (node (ref "U21") (pin "3") (pinfunction "RESERVED_3") (pintype "passive+no_connect"))
    )
    (net (code "51") (name "unconnected-(U21A-RESERVED-Pad4)") (class "Default")
      (node (ref "U21") (pin "4") (pinfunction "RESERVED_4") (pintype "passive+no_connect"))
    )
    (net (code "52") (name "unconnected-(U21A-RESERVED-Pad5)") (class "Default")
      (node (ref "U21") (pin "5") (pinfunction "RESERVED_5") (pintype "passive+no_connect"))
    )
    (net (code "53") (name "unconnected-(U21A-RESERVED-Pad6)") (class "Default")
      (node (ref "U21") (pin "6") (pinfunction "RESERVED_6") (pintype "passive+no_connect"))
    )
    (net (code "54") (name "unconnected-(U21A-RESERVED-Pad8)") (class "Default")
      (node (ref "U21") (pin "8") (pinfunction "RESERVED_8") (pintype "passive+no_connect"))
    )
    (net (code "55") (name "unconnected-(U21A-RESERVED-Pad21)") (class "Default")
      (node (ref "U21") (pin "21") (pinfunction "RESERVED_21") (pintype "passive+no_connect"))
    )
    (net (code "56") (name "unconnected-(U21A-RESERVED-Pad22)") (class "Default")
      (node (ref "U21") (pin "22") (pinfunction "RESERVED_22") (pintype "passive+no_connect"))
    )
    (net (code "57") (name "unconnected-(U21A-RESERVED-Pad23)") (class "Default")
      (node (ref "U21") (pin "23") (pinfunction "RESERVED_23") (pintype "passive+no_connect"))
    )
    (net (code "58") (name "unconnected-(U21A-RESERVED-Pad25)") (class "Default")
      (node (ref "U21") (pin "25") (pinfunction "RESERVED_25") (pintype "passive+no_connect"))
    )
    (net (code "59") (name "unconnected-(U21A-RESERVED-Pad26)") (class "Default")
      (node (ref "U21") (pin "26") (pinfunction "RESERVED_26") (pintype "passive+no_connect"))
    )
    (net (code "60") (name "unconnected-(U21A-RESERVED-Pad28)") (class "Default")
      (node (ref "U21") (pin "28") (pinfunction "RESERVED_28") (pintype "passive+no_connect"))
    )
    (net (code "61") (name "unconnected-(U21A-RESERVED-Pad29)") (class "Default")
      (node (ref "U21") (pin "29") (pinfunction "RESERVED_29") (pintype "passive+no_connect"))
    )
    (net (code "62") (name "unconnected-(U21A-RESERVED-Pad30)") (class "Default")
      (node (ref "U21") (pin "30") (pinfunction "RESERVED_30") (pintype "passive+no_connect"))
    )
    (net (code "63") (name "unconnected-(U21A-RESERVED-Pad31)") (class "Default")
      (node (ref "U21") (pin "31") (pinfunction "RESERVED_31") (pintype "passive+no_connect"))
    )
    (net (code "64") (name "unconnected-(U21A-RESERVED-Pad32)") (class "Default")
      (node (ref "U21") (pin "32") (pinfunction "RESERVED_32") (pintype "passive+no_connect"))
    )
    (net (code "65") (name "unconnected-(U21A-RESERVED-Pad33)") (class "Default")
      (node (ref "U21") (pin "33") (pinfunction "RESERVED_33") (pintype "passive+no_connect"))
    )
    (net (code "66") (name "unconnected-(U21A-RESERVED-Pad44)") (class "Default")
      (node (ref "U21") (pin "44") (pinfunction "RESERVED_44") (pintype "passive+no_connect"))
    )
    (net (code "67") (name "unconnected-(U21A-RI-Pad20)") (class "Default")
      (node (ref "U21") (pin "20") (pinfunction "RI_20") (pintype "passive+no_connect"))
    )
    (net (code "68") (name "unconnected-(U21B-RESERVED-Pad45)") (class "Default")
      (node (ref "U21") (pin "45") (pinfunction "RESERVED_45") (pintype "passive+no_connect"))
    )
    (net (code "69") (name "unconnected-(U21B-RESERVED-Pad46)") (class "Default")
      (node (ref "U21") (pin "46") (pinfunction "RESERVED_46") (pintype "passive+no_connect"))
    )
    (net (code "70") (name "unconnected-(U21B-RESERVED-Pad47)") (class "Default")
      (node (ref "U21") (pin "47") (pinfunction "RESERVED_47") (pintype "passive+no_connect"))
    )
    (net (code "71") (name "unconnected-(U21B-RESERVED-Pad48)") (class "Default")
      (node (ref "U21") (pin "48") (pinfunction "RESERVED_48") (pintype "passive+no_connect"))
    )
    (net (code "72") (name "unconnected-(U21B-RESERVED-Pad49)") (class "Default")
      (node (ref "U21") (pin "49") (pinfunction "RESERVED_49") (pintype "passive"))
    )
    (net (code "73") (name "unconnected-(U21B-RESERVED-Pad50)") (class "Default")
      (node (ref "U21") (pin "50") (pinfunction "RESERVED_50") (pintype "passive"))
    )
    (net (code "74") (name "unconnected-(U21B-RESERVED-Pad51)") (class "Default")
      (node (ref "U21") (pin "51") (pinfunction "RESERVED_51") (pintype "passive"))
    )
    (net (code "75") (name "unconnected-(U21B-RESERVED-Pad52)") (class "Default")
      (node (ref "U21") (pin "52") (pinfunction "RESERVED_52") (pintype "passive+no_connect"))
    )
    (net (code "76") (name "unconnected-(U21B-RESERVED-Pad53)") (class "Default")
      (node (ref "U21") (pin "53") (pinfunction "RESERVED_53") (pintype "passive+no_connect"))
    )
    (net (code "77") (name "unconnected-(U21B-RESERVED-Pad54)") (class "Default")
      (node (ref "U21") (pin "54") (pinfunction "RESERVED_54") (pintype "passive+no_connect"))
    )
    (net (code "78") (name "unconnected-(U21B-RESERVED-Pad55)") (class "Default")
      (node (ref "U21") (pin "55") (pinfunction "RESERVED_55") (pintype "passive+no_connect"))
    )
    (net (code "79") (name "unconnected-(U21B-RESERVED-Pad56)") (class "Default")
      (node (ref "U21") (pin "56") (pinfunction "RESERVED_56") (pintype "passive+no_connect"))
    )
    (net (code "80") (name "unconnected-(U21B-RESERVED-Pad57)") (class "Default")
      (node (ref "U21") (pin "57") (pinfunction "RESERVED_57") (pintype "passive+no_connect"))
    )
    (net (code "81") (name "unconnected-(U21B-RESERVED-Pad58)") (class "Default")
      (node (ref "U21") (pin "58") (pinfunction "RESERVED_58") (pintype "passive+no_connect"))
    )
  )
)
